# adc.net
KiCad netlist of a schematic drawn in Altium Designer
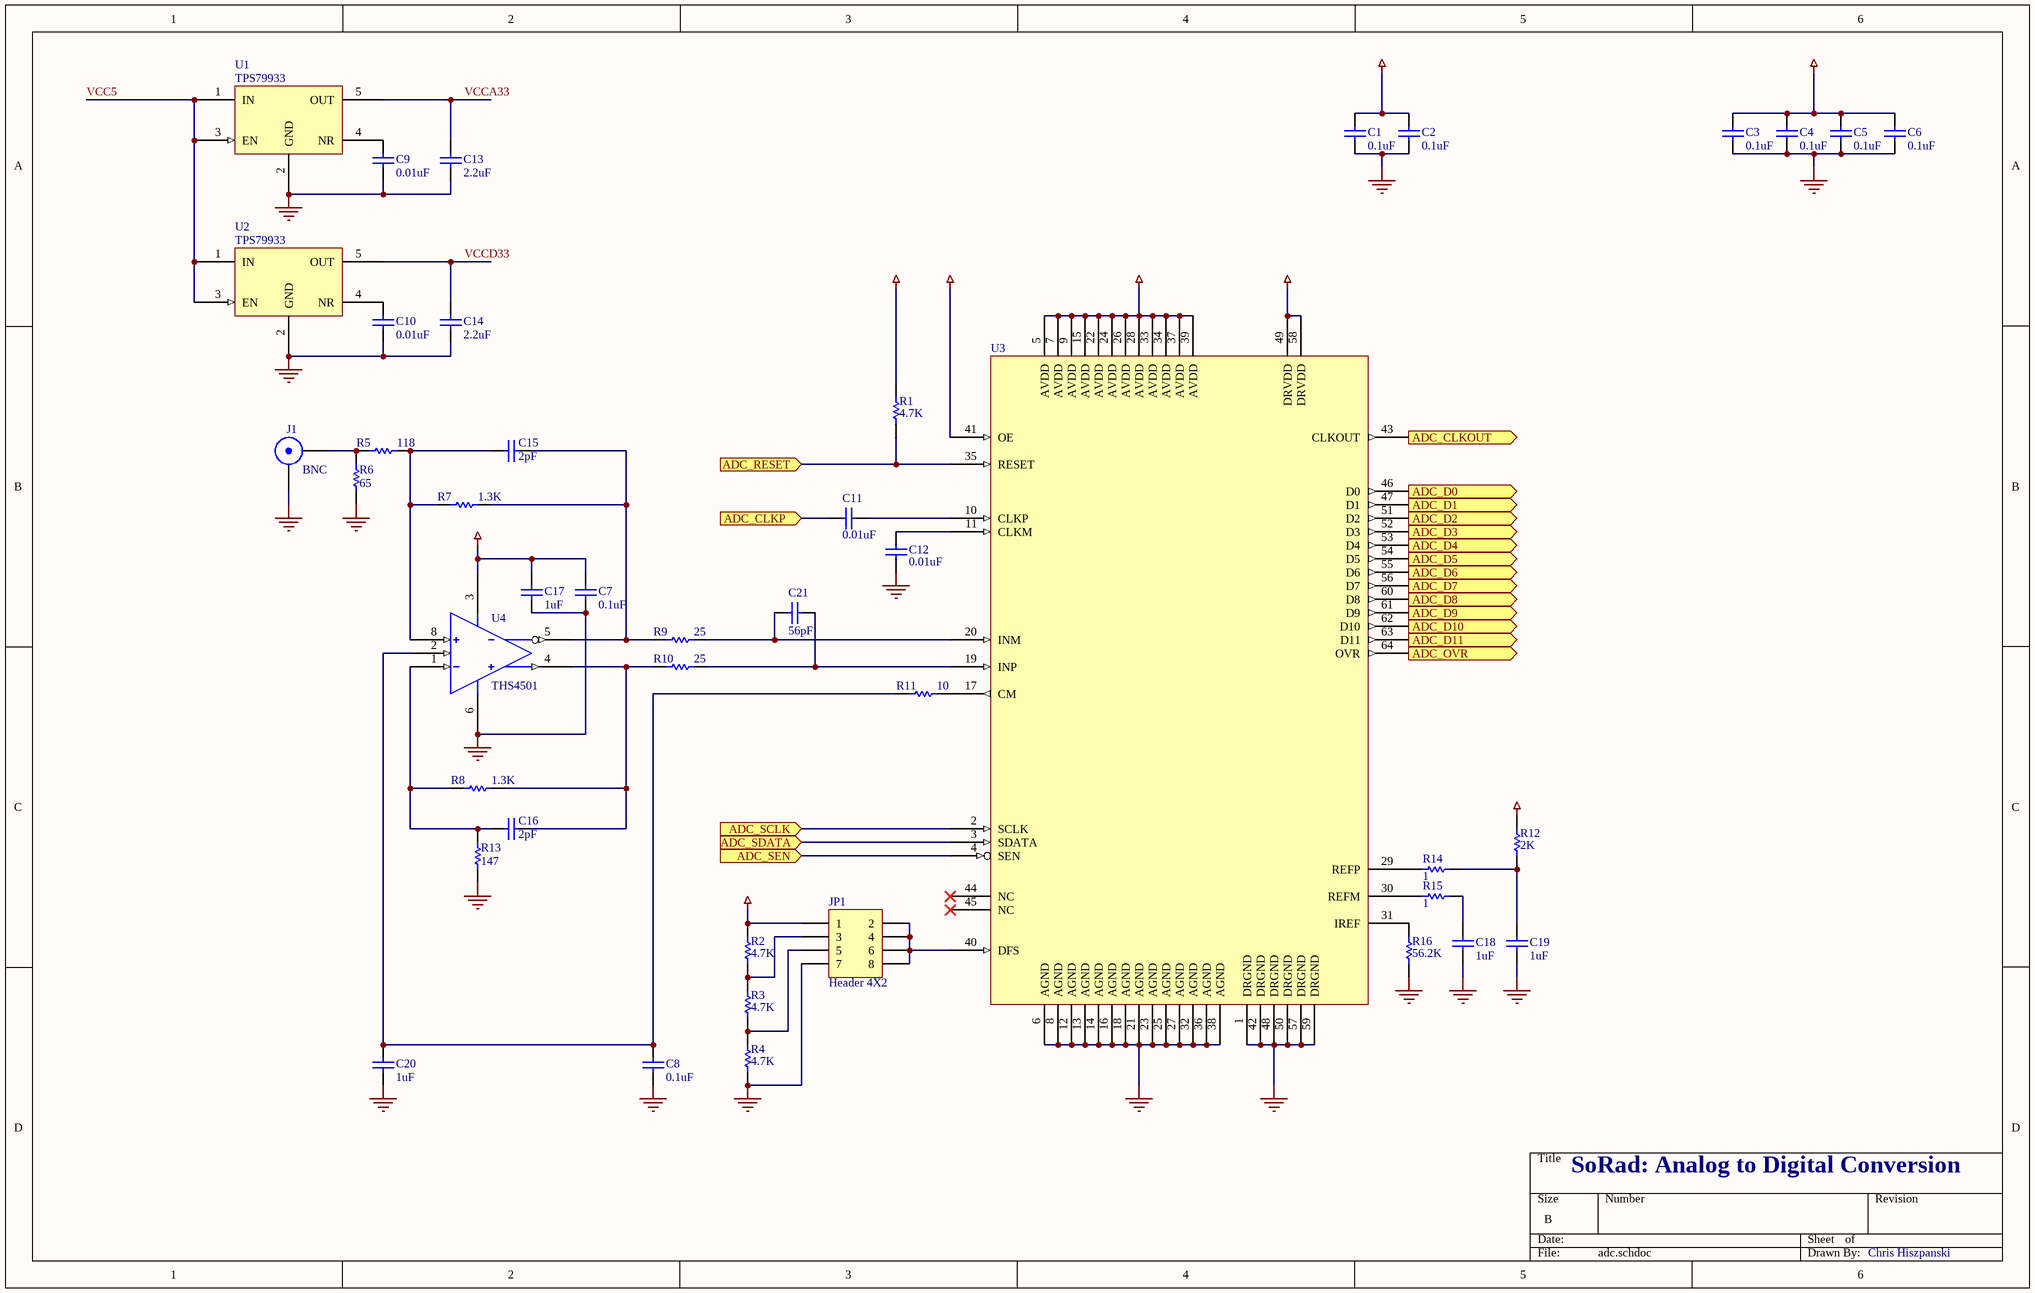
[diagram p0: adc.schdoc]

(export (version "E")
  (design (tool "Eeschema 10.0.6"))
  (components
    (comp (ref "C1")
      (value "0.1uF")
      (footprint "CC2012-0805")
      (description "Capacitor")
      (fields
        (field (name "DISTRIBUTOR PART NUMBER") "PCC1843CT-ND")
        (field (name "MANUFACTURER") "Panasonic")
        (field (name "PUBLISHER") "Altium Limited")
      )
      (libsource (lib "Miscellaneous Devices") (part "Cap"))
    )
    (comp (ref "C2")
      (value "0.1uF")
      (footprint "CC2012-0805")
      (description "Capacitor")
      (fields
        (field (name "DISTRIBUTOR PART NUMBER") "PCC1843CT-ND")
        (field (name "MANUFACTURER") "Panasonic")
        (field (name "PUBLISHER") "Altium Limited")
      )
      (libsource (lib "Miscellaneous Devices") (part "Cap"))
    )
    (comp (ref "C3")
      (value "0.1uF")
      (footprint "CC2012-0805")
      (description "Capacitor")
      (fields
        (field (name "DISTRIBUTOR PART NUMBER") "PCC1843CT-ND")
        (field (name "MANUFACTURER") "Panasonic")
        (field (name "PUBLISHER") "Altium Limited")
      )
      (libsource (lib "Miscellaneous Devices") (part "Cap"))
    )
    (comp (ref "C4")
      (value "0.1uF")
      (footprint "CC2012-0805")
      (description "Capacitor")
      (fields
        (field (name "DISTRIBUTOR PART NUMBER") "PCC1843CT-ND")
        (field (name "MANUFACTURER") "Panasonic")
        (field (name "PUBLISHER") "Altium Limited")
      )
      (libsource (lib "Miscellaneous Devices") (part "Cap"))
    )
    (comp (ref "C5")
      (value "0.1uF")
      (footprint "CC2012-0805")
      (description "Capacitor")
      (fields
        (field (name "DISTRIBUTOR PART NUMBER") "PCC1843CT-ND")
        (field (name "MANUFACTURER") "Panasonic")
        (field (name "PUBLISHER") "Altium Limited")
      )
      (libsource (lib "Miscellaneous Devices") (part "Cap"))
    )
    (comp (ref "C6")
      (value "0.1uF")
      (footprint "CC2012-0805")
      (description "Capacitor")
      (fields
        (field (name "DISTRIBUTOR PART NUMBER") "PCC1843CT-ND")
        (field (name "MANUFACTURER") "Panasonic")
        (field (name "PUBLISHER") "Altium Limited")
      )
      (libsource (lib "Miscellaneous Devices") (part "Cap"))
    )
    (comp (ref "C7")
      (value "0.1uF")
      (footprint "CC2012-0805")
      (description "Capacitor")
      (fields
        (field (name "DISTRIBUTOR PART NUMBER") "PCC1843CT-ND")
        (field (name "MANUFACTURER") "Panasonic")
        (field (name "PUBLISHER") "Altium Limited")
      )
      (libsource (lib "Miscellaneous Devices") (part "Cap"))
    )
    (comp (ref "C8")
      (value "0.1uF")
      (footprint "CC2012-0805")
      (description "Capacitor")
      (fields
        (field (name "DISTRIBUTOR PART NUMBER") "PCC1843CT-ND")
        (field (name "MANUFACTURER") "Panasonic")
        (field (name "PUBLISHER") "Altium Limited")
      )
      (libsource (lib "Miscellaneous Devices") (part "Cap"))
    )
    (comp (ref "C9")
      (value "0.01uF")
      (footprint "CC2012-0805")
      (description "Capacitor")
      (fields
        (field (name "DISTRIBUTOR PART NUMBER") "PCC1858CT-ND")
        (field (name "MANUFACTURER") "Panasonic")
        (field (name "PUBLISHER") "Altium Limited")
      )
      (libsource (lib "Miscellaneous Devices") (part "Cap"))
    )
    (comp (ref "C10")
      (value "0.01uF")
      (footprint "CC2012-0805")
      (description "Capacitor")
      (fields
        (field (name "DISTRIBUTOR PART NUMBER") "PCC1858CT-ND")
        (field (name "MANUFACTURER") "Panasonic")
        (field (name "PUBLISHER") "Altium Limited")
      )
      (libsource (lib "Miscellaneous Devices") (part "Cap"))
    )
    (comp (ref "C11")
      (value "0.01uF")
      (footprint "CC2012-0805")
      (description "Capacitor")
      (fields
        (field (name "DISTRIBUTOR PART NUMBER") "PCC1858CT-ND")
        (field (name "MANUFACTURER") "Panasonic")
        (field (name "PUBLISHER") "Altium Limited")
      )
      (libsource (lib "Miscellaneous Devices") (part "Cap"))
    )
    (comp (ref "C12")
      (value "0.01uF")
      (footprint "CC2012-0805")
      (description "Capacitor")
      (fields
        (field (name "DISTRIBUTOR PART NUMBER") "PCC1858CT-ND")
        (field (name "MANUFACTURER") "Panasonic")
        (field (name "PUBLISHER") "Altium Limited")
      )
      (libsource (lib "Miscellaneous Devices") (part "Cap"))
    )
    (comp (ref "C13")
      (value "2.2uF")
      (footprint "CC3216-1206")
      (description "Capacitor")
      (fields
        (field (name "DISTRIBUTOR PART NUMBER") "PCC1898CT-ND")
        (field (name "MANUFACTURER") "Panasonic")
        (field (name "PUBLISHER") "Altium Limited")
      )
      (libsource (lib "Miscellaneous Devices") (part "Cap"))
    )
    (comp (ref "C14")
      (value "2.2uF")
      (footprint "CC3216-1206")
      (description "Capacitor")
      (fields
        (field (name "DISTRIBUTOR PART NUMBER") "PCC1898CT-ND")
        (field (name "MANUFACTURER") "Panasonic")
        (field (name "PUBLISHER") "Altium Limited")
      )
      (libsource (lib "Miscellaneous Devices") (part "Cap"))
    )
    (comp (ref "C15")
      (value "2pF")
      (footprint "CC2012-0805")
      (description "Capacitor")
      (fields
        (field (name "DISTRIBUTOR PART NUMBER") "338-1096-ND")
        (field (name "MANUFACTURER") "Cornell Dubilier")
        (field (name "PUBLISHER") "Altium Limited")
      )
      (libsource (lib "Miscellaneous Devices") (part "Cap"))
    )
    (comp (ref "C16")
      (value "2pF")
      (footprint "CC2012-0805")
      (description "Capacitor")
      (fields
        (field (name "DISTRIBUTOR PART NUMBER") "338-1096-ND")
        (field (name "MANUFACTURER") "Cornell Dubilier")
        (field (name "PUBLISHER") "Altium Limited")
      )
      (libsource (lib "Miscellaneous Devices") (part "Cap"))
    )
    (comp (ref "C17")
      (value "1uF")
      (footprint "CC2012-0805")
      (description "Capacitor")
      (fields
        (field (name "MANUFACTURER") "Panasonic")
        (field (name "DISTRIBUTOR PART NUMBER") "PCC1849CT-ND")
        (field (name "PUBLISHER") "Altium Limited")
      )
      (libsource (lib "Miscellaneous Devices") (part "Cap"))
    )
    (comp (ref "C18")
      (value "1uF")
      (footprint "CC2012-0805")
      (description "Capacitor")
      (fields
        (field (name "MANUFACTURER") "Panasonic")
        (field (name "DISTRIBUTOR PART NUMBER") "PCC1849CT-ND")
        (field (name "PUBLISHER") "Altium Limited")
      )
      (libsource (lib "Miscellaneous Devices") (part "Cap"))
    )
    (comp (ref "C19")
      (value "1uF")
      (footprint "CC2012-0805")
      (description "Capacitor")
      (fields
        (field (name "MANUFACTURER") "Panasonic")
        (field (name "DISTRIBUTOR PART NUMBER") "PCC1849CT-ND")
        (field (name "PUBLISHER") "Altium Limited")
      )
      (libsource (lib "Miscellaneous Devices") (part "Cap"))
    )
    (comp (ref "C20")
      (value "1uF")
      (footprint "CC2012-0805")
      (description "Capacitor")
      (fields
        (field (name "MANUFACTURER") "Panasonic")
        (field (name "DISTRIBUTOR PART NUMBER") "PCC1849CT-ND")
        (field (name "PUBLISHER") "Altium Limited")
      )
      (libsource (lib "Miscellaneous Devices") (part "Cap"))
    )
    (comp (ref "C21")
      (value "56pF")
      (footprint "CC2012-0805")
      (description "Capacitor")
      (fields
        (field (name "DISTRIBUTOR PART NUMBER") "311-1108-1-ND")
        (field (name "MANUFACTURER") "Yageo")
        (field (name "PUBLISHER") "Altium Limited")
      )
      (libsource (lib "Miscellaneous Devices") (part "Cap"))
    )
    (comp (ref "J1")
      (value "BNC")
      (footprint "BNC_RA CON")
      (description "BNC Elbow Connector")
      (fields
        (field (name "DISTRIBUTOR PART NUMBER") "A24486-ND")
        (field (name "MANUFACTURER") "Amp")
        (field (name "PUBLISHER") "Altium Limited")
      )
      (libsource (lib "Miscellaneous Connectors") (part "BNC"))
    )
    (comp (ref "JP1")
      (value "Header 4X2")
      (footprint "HDR2X4")
      (description "Header, 4-Pin, Dual row")
      (fields (field (name "DISTRIBUTOR PART NUMBER") "NA") (field (name "PUBLISHER") "Altium Limited"))
      (libsource (lib "Miscellaneous Connectors") (part "Header 4X2"))
    )
    (comp (ref "R1")
      (value "4.7K")
      (footprint "CR2012-0805")
      (description "Resistor")
      (fields
        (field (name "MANUFACTURER") "Generic Components")
        (field (name "DISTRIBUTOR PART NUMBER") "541-4.7KACT-ND")
        (field (name "PUBLISHER") "Altium Limited")
      )
      (libsource (lib "") (part "Res1_1"))
    )
    (comp (ref "R2")
      (value "4.7K")
      (footprint "CR2012-0805")
      (description "Resistor")
      (fields
        (field (name "MANUFACTURER") "Generic Components")
        (field (name "DISTRIBUTOR PART NUMBER") "541-4.7KACT-ND")
        (field (name "PUBLISHER") "Altium Limited")
      )
      (libsource (lib "") (part "Res1_1"))
    )
    (comp (ref "R3")
      (value "4.7K")
      (footprint "CR2012-0805")
      (description "Resistor")
      (fields
        (field (name "MANUFACTURER") "Generic Components")
        (field (name "DISTRIBUTOR PART NUMBER") "541-4.7KACT-ND")
        (field (name "PUBLISHER") "Altium Limited")
      )
      (libsource (lib "") (part "Res1_1"))
    )
    (comp (ref "R4")
      (value "4.7K")
      (footprint "CR2012-0805")
      (description "Resistor")
      (fields
        (field (name "MANUFACTURER") "Generic Components")
        (field (name "DISTRIBUTOR PART NUMBER") "541-4.7KACT-ND")
        (field (name "PUBLISHER") "Altium Limited")
      )
      (libsource (lib "") (part "Res1_1"))
    )
    (comp (ref "R5")
      (value "118")
      (footprint "CC2012-0805")
      (description "Resistor")
      (fields
        (field (name "DISTRIBUTOR PART NUMBER") "311-118CCT-ND")
        (field (name "MANUFACTURER") "Yageo")
        (field (name "PUBLISHER") "Altium Limited")
      )
      (libsource (lib "Miscellaneous Devices") (part "Res1"))
    )
    (comp (ref "R6")
      (value "65")
      (footprint "CC2012-0805")
      (description "Resistor")
      (fields
        (field (name "DISTRIBUTOR PART NUMBER") "311-64.9CCT-ND")
        (field (name "MANUFACTURER") "Yageo")
        (field (name "PUBLISHER") "Altium Limited")
      )
      (libsource (lib "Miscellaneous Devices") (part "Res1"))
    )
    (comp (ref "R7")
      (value "1.3K")
      (footprint "CC2012-0805")
      (description "Resistor")
      (fields
        (field (name "DISTRIBUTOR PART NUMBER") "RHM1.30KCCT-ND")
        (field (name "MANUFACTURER") "Rohm")
        (field (name "PUBLISHER") "Altium Limited")
      )
      (libsource (lib "Miscellaneous Devices") (part "Res1"))
    )
    (comp (ref "R8")
      (value "1.3K")
      (footprint "CC2012-0805")
      (description "Resistor")
      (fields
        (field (name "DISTRIBUTOR PART NUMBER") "RHM1.30KCCT-ND")
        (field (name "MANUFACTURER") "Rohm")
        (field (name "PUBLISHER") "Altium Limited")
      )
      (libsource (lib "Miscellaneous Devices") (part "Res1"))
    )
    (comp (ref "R9")
      (value "25")
      (footprint "CC2012-0805")
      (description "Resistor")
      (fields
        (field (name "DISTRIBUTOR PART NUMBER") "541-24.9CCT-ND")
        (field (name "MANUFACTURER") "Vishay/Dale")
        (field (name "PUBLISHER") "Altium Limited")
      )
      (libsource (lib "Miscellaneous Devices") (part "Res1"))
    )
    (comp (ref "R10")
      (value "25")
      (footprint "CC2012-0805")
      (description "Resistor")
      (fields
        (field (name "DISTRIBUTOR PART NUMBER") "541-24.9CCT-ND")
        (field (name "MANUFACTURER") "Vishay/Dale")
        (field (name "PUBLISHER") "Altium Limited")
      )
      (libsource (lib "Miscellaneous Devices") (part "Res1"))
    )
    (comp (ref "R11")
      (value "10")
      (footprint "CC2012-0805")
      (description "Resistor")
      (fields
        (field (name "DISTRIBUTOR PART NUMBER") "311-10.0CRCT-ND")
        (field (name "MANUFACTURER") "Yageo")
        (field (name "PUBLISHER") "Altium Limited")
      )
      (libsource (lib "Miscellaneous Devices") (part "Res1"))
    )
    (comp (ref "R12")
      (value "2K")
      (footprint "CC2012-0805")
      (description "Resistor")
      (fields
        (field (name "DISTRIBUTOR PART NUMBER") "311-2.00KCRCT-ND")
        (field (name "MANUFACTURER") "Yageo")
        (field (name "PUBLISHER") "Altium Limited")
      )
      (libsource (lib "Miscellaneous Devices") (part "Res1"))
    )
    (comp (ref "R13")
      (value "147")
      (footprint "CC2012-0805")
      (description "Resistor")
      (fields
        (field (name "MANUFACTURER") "Yageo")
        (field (name "DISTRIBUTOR PART NUMBER") "311-147CRCT-ND")
        (field (name "PUBLISHER") "Altium Limited")
      )
      (libsource (lib "Miscellaneous Devices") (part "Res1"))
    )
    (comp (ref "R14")
      (value "1")
      (footprint "CC2012-0805")
      (description "Resistor")
      (fields
        (field (name "DISTRIBUTOR PART NUMBER") "311-1.00CRCT-ND")
        (field (name "MANUFACTURER") "Yageo")
        (field (name "PUBLISHER") "Altium Limited")
      )
      (libsource (lib "Miscellaneous Devices") (part "Res1"))
    )
    (comp (ref "R15")
      (value "1")
      (footprint "CC2012-0805")
      (description "Resistor")
      (fields
        (field (name "DISTRIBUTOR PART NUMBER") "311-1.00CRCT-ND")
        (field (name "MANUFACTURER") "Yageo")
        (field (name "PUBLISHER") "Altium Limited")
      )
      (libsource (lib "Miscellaneous Devices") (part "Res1"))
    )
    (comp (ref "R16")
      (value "56.2K")
      (footprint "CC2012-0805")
      (description "Resistor")
      (fields
        (field (name "DISTRIBUTOR PART NUMBER") "311-56.2KCRCT-ND")
        (field (name "MANUFACTURER") "Yageo")
        (field (name "PUBLISHER") "Altium Limited")
      )
      (libsource (lib "Miscellaneous Devices") (part "Res1"))
    )
    (comp (ref "U1")
      (value "TPS79933")
      (footprint "SO-G5/P.95")
      (description "LDO Voltage Regulator")
      (fields
        (field (name "DISTRIBUTOR PART NUMBER") "296-17783-1-ND")
        (field (name "MANUFACTURER") "Texas Instruments")
      )
      (libsource (lib "minisdr") (part "TPS799xx"))
    )
    (comp (ref "U2")
      (value "TPS79933")
      (footprint "SO-G5/P.95")
      (description "LDO Voltage Regulator")
      (fields
        (field (name "DISTRIBUTOR PART NUMBER") "296-17783-1-ND")
        (field (name "MANUFACTURER") "Texas Instruments")
      )
      (libsource (lib "minisdr") (part "TPS799xx"))
    )
    (comp (ref "U3")
      (value "~")
      (footprint "HQFP64")
      (description "ADC 12BIT 125MSPS")
      (fields
        (field (name "MANUFACTURER") "Texas Instruments")
        (field (name "MANUFACTURER PART NUMBER") "ADS5520IPAP")
      )
      (libsource (lib "minisdr") (part "ADS5520"))
    )
    (comp (ref "U4")
      (value "THS4501")
      (footprint "SOIC8")
      (description "Differential Amplifier")
      (fields
        (field (name "DISTRIBUTOR PART NUMBER") "296-12936-5-ND")
        (field (name "MANUFACTURER") "Texas Instruments")
      )
      (libsource (lib "minisdr") (part "THS4501"))
    )
  )
  (nets
    (net (code "1") (name "/ADC_CLKOUT") (class "Default")
      (node (ref "U3") (pin "43") (pinfunction "CLKOUT_43") (pintype "output"))
    )
    (net (code "2") (name "/ADC_CLKP") (class "Default")
      (node (ref "C11") (pin "2") (pinfunction "2_2") (pintype "passive"))
    )
    (net (code "3") (name "/ADC_D0") (class "Default")
      (node (ref "U3") (pin "46") (pinfunction "D0_46") (pintype "output"))
    )
    (net (code "4") (name "/ADC_D1") (class "Default")
      (node (ref "U3") (pin "47") (pinfunction "D1_47") (pintype "output"))
    )
    (net (code "5") (name "/ADC_D2") (class "Default")
      (node (ref "U3") (pin "51") (pinfunction "D2_51") (pintype "output"))
    )
    (net (code "6") (name "/ADC_D3") (class "Default")
      (node (ref "U3") (pin "52") (pinfunction "D3_52") (pintype "output"))
    )
    (net (code "7") (name "/ADC_D4") (class "Default")
      (node (ref "U3") (pin "53") (pinfunction "D4_53") (pintype "output"))
    )
    (net (code "8") (name "/ADC_D5") (class "Default")
      (node (ref "U3") (pin "54") (pinfunction "D5_54") (pintype "output"))
    )
    (net (code "9") (name "/ADC_D6") (class "Default")
      (node (ref "U3") (pin "55") (pinfunction "D6_55") (pintype "output"))
    )
    (net (code "10") (name "/ADC_D7") (class "Default")
      (node (ref "U3") (pin "56") (pinfunction "D7_56") (pintype "output"))
    )
    (net (code "11") (name "/ADC_D8") (class "Default")
      (node (ref "U3") (pin "60") (pinfunction "D8_60") (pintype "output"))
    )
    (net (code "12") (name "/ADC_D9") (class "Default")
      (node (ref "U3") (pin "61") (pinfunction "D9_61") (pintype "output"))
    )
    (net (code "13") (name "/ADC_D10") (class "Default")
      (node (ref "U3") (pin "62") (pinfunction "D10_62") (pintype "output"))
    )
    (net (code "14") (name "/ADC_D11") (class "Default")
      (node (ref "U3") (pin "63") (pinfunction "D11_63") (pintype "output"))
    )
    (net (code "15") (name "/ADC_OVR") (class "Default")
      (node (ref "U3") (pin "64") (pinfunction "OVR_64") (pintype "output"))
    )
    (net (code "16") (name "/ADC_RESET") (class "Default")
      (node (ref "R1") (pin "1") (pinfunction "1_1") (pintype "passive"))
      (node (ref "U3") (pin "35") (pinfunction "RESET_35") (pintype "input"))
    )
    (net (code "17") (name "/ADC_SCLK") (class "Default")
      (node (ref "U3") (pin "2") (pinfunction "SCLK_2") (pintype "input"))
    )
    (net (code "18") (name "/ADC_SDATA") (class "Default")
      (node (ref "U3") (pin "3") (pinfunction "SDATA_3") (pintype "input"))
    )
    (net (code "19") (name "/ADC_SEN") (class "Default")
      (node (ref "U3") (pin "4") (pinfunction "SEN_4") (pintype "input"))
    )
    (net (code "20") (name "GND") (class "Default")
      (node (ref "C1") (pin "1") (pinfunction "1_1") (pintype "passive"))
      (node (ref "C10") (pin "1") (pinfunction "1_1") (pintype "passive"))
      (node (ref "C12") (pin "2") (pinfunction "2_2") (pintype "passive"))
      (node (ref "C13") (pin "1") (pinfunction "1_1") (pintype "passive"))
      (node (ref "C14") (pin "1") (pinfunction "1_1") (pintype "passive"))
      (node (ref "C17") (pin "1") (pinfunction "1_1") (pintype "passive"))
      (node (ref "C18") (pin "1") (pinfunction "1_1") (pintype "passive"))
      (node (ref "C19") (pin "1") (pinfunction "1_1") (pintype "passive"))
      (node (ref "C2") (pin "1") (pinfunction "1_1") (pintype "passive"))
      (node (ref "C20") (pin "1") (pinfunction "1_1") (pintype "passive"))
      (node (ref "C3") (pin "1") (pinfunction "1_1") (pintype "passive"))
      (node (ref "C4") (pin "1") (pinfunction "1_1") (pintype "passive"))
      (node (ref "C5") (pin "1") (pinfunction "1_1") (pintype "passive"))
      (node (ref "C6") (pin "1") (pinfunction "1_1") (pintype "passive"))
      (node (ref "C7") (pin "1") (pinfunction "1_1") (pintype "passive"))
      (node (ref "C8") (pin "1") (pinfunction "1_1") (pintype "passive"))
      (node (ref "C9") (pin "1") (pinfunction "1_1") (pintype "passive"))
      (node (ref "J1") (pin "2") (pinfunction "Y_2") (pintype "passive"))
      (node (ref "JP1") (pin "7") (pinfunction "7_7") (pintype "passive"))
      (node (ref "R13") (pin "2") (pinfunction "2_2") (pintype "passive"))
      (node (ref "R16") (pin "2") (pinfunction "2_2") (pintype "passive"))
      (node (ref "R4") (pin "1") (pinfunction "1_1") (pintype "passive"))
      (node (ref "R6") (pin "2") (pinfunction "2_2") (pintype "passive"))
      (node (ref "U1") (pin "2") (pinfunction "GND_2") (pintype "power_in"))
      (node (ref "U2") (pin "2") (pinfunction "GND_2") (pintype "power_in"))
      (node (ref "U3") (pin "1") (pinfunction "DRGND_1") (pintype "power_in"))
      (node (ref "U3") (pin "12") (pinfunction "AGND_12") (pintype "power_in"))
      (node (ref "U3") (pin "13") (pinfunction "AGND_13") (pintype "power_in"))
      (node (ref "U3") (pin "14") (pinfunction "AGND_14") (pintype "power_in"))
      (node (ref "U3") (pin "16") (pinfunction "AGND_16") (pintype "power_in"))
      (node (ref "U3") (pin "18") (pinfunction "AGND_18") (pintype "power_in"))
      (node (ref "U3") (pin "21") (pinfunction "AGND_21") (pintype "power_in"))
      (node (ref "U3") (pin "23") (pinfunction "AGND_23") (pintype "power_in"))
      (node (ref "U3") (pin "25") (pinfunction "AGND_25") (pintype "power_in"))
      (node (ref "U3") (pin "27") (pinfunction "AGND_27") (pintype "power_in"))
      (node (ref "U3") (pin "32") (pinfunction "AGND_32") (pintype "power_in"))
      (node (ref "U3") (pin "36") (pinfunction "AGND_36") (pintype "power_in"))
      (node (ref "U3") (pin "38") (pinfunction "AGND_38") (pintype "power_in"))
      (node (ref "U3") (pin "42") (pinfunction "DRGND_42") (pintype "power_in"))
      (node (ref "U3") (pin "48") (pinfunction "DRGND_48") (pintype "power_in"))
      (node (ref "U3") (pin "50") (pinfunction "DRGND_50") (pintype "power_in"))
      (node (ref "U3") (pin "57") (pinfunction "DRGND_57") (pintype "power_in"))
      (node (ref "U3") (pin "59") (pinfunction "DRGND_59") (pintype "power_in"))
      (node (ref "U3") (pin "6") (pinfunction "AGND_6") (pintype "power_in"))
      (node (ref "U3") (pin "8") (pinfunction "AGND_8") (pintype "power_in"))
      (node (ref "U4") (pin "6") (pinfunction "Vs-_6") (pintype "power_in"))
    )
    (net (code "21") (name "Net-(C18-Pad2)") (class "Default")
      (node (ref "C18") (pin "2") (pinfunction "2_2") (pintype "passive"))
      (node (ref "R15") (pin "2") (pinfunction "2_2") (pintype "passive"))
    )
    (net (code "22") (name "Net-(C19-Pad2)") (class "Default")
      (node (ref "C19") (pin "2") (pinfunction "2_2") (pintype "passive"))
      (node (ref "R12") (pin "2") (pinfunction "2_2") (pintype "passive"))
      (node (ref "R14") (pin "2") (pinfunction "2_2") (pintype "passive"))
    )
    (net (code "23") (name "Net-(J1-X)") (class "Default")
      (node (ref "J1") (pin "1") (pinfunction "X_1") (pintype "passive"))
      (node (ref "R5") (pin "2") (pinfunction "2_2") (pintype "passive"))
      (node (ref "R6") (pin "1") (pinfunction "1_1") (pintype "passive"))
    )
    (net (code "24") (name "Net-(JP1-Pad3)") (class "Default")
      (node (ref "JP1") (pin "3") (pinfunction "3_3") (pintype "passive"))
      (node (ref "R2") (pin "1") (pinfunction "1_1") (pintype "passive"))
      (node (ref "R3") (pin "2") (pinfunction "2_2") (pintype "passive"))
    )
    (net (code "25") (name "Net-(JP1-Pad5)") (class "Default")
      (node (ref "JP1") (pin "5") (pinfunction "5_5") (pintype "passive"))
      (node (ref "R3") (pin "1") (pinfunction "1_1") (pintype "passive"))
      (node (ref "R4") (pin "2") (pinfunction "2_2") (pintype "passive"))
    )
    (net (code "26") (name "Net-(U1-NR)") (class "Default")
      (node (ref "C9") (pin "2") (pinfunction "2_2") (pintype "passive"))
      (node (ref "U1") (pin "4") (pinfunction "NR_4") (pintype "passive"))
    )
    (net (code "27") (name "Net-(U2-NR)") (class "Default")
      (node (ref "C10") (pin "2") (pinfunction "2_2") (pintype "passive"))
      (node (ref "U2") (pin "4") (pinfunction "NR_4") (pintype "passive"))
    )
    (net (code "28") (name "Net-(U3-CLKM)") (class "Default")
      (node (ref "C12") (pin "1") (pinfunction "1_1") (pintype "passive"))
      (node (ref "U3") (pin "11") (pinfunction "CLKM_11") (pintype "input"))
    )
    (net (code "29") (name "Net-(U3-CLKP)") (class "Default")
      (node (ref "C11") (pin "1") (pinfunction "1_1") (pintype "passive"))
      (node (ref "U3") (pin "10") (pinfunction "CLKP_10") (pintype "input"))
    )
    (net (code "30") (name "Net-(U3-CM)") (class "Default")
      (node (ref "R11") (pin "1") (pinfunction "1_1") (pintype "passive"))
      (node (ref "U3") (pin "17") (pinfunction "CM_17") (pintype "output"))
    )
    (net (code "31") (name "Net-(U3-DFS)") (class "Default")
      (node (ref "JP1") (pin "2") (pinfunction "2_2") (pintype "passive"))
      (node (ref "JP1") (pin "4") (pinfunction "4_4") (pintype "passive"))
      (node (ref "JP1") (pin "6") (pinfunction "6_6") (pintype "passive"))
      (node (ref "JP1") (pin "8") (pinfunction "8_8") (pintype "passive"))
      (node (ref "U3") (pin "40") (pinfunction "DFS_40") (pintype "input"))
    )
    (net (code "32") (name "Net-(U3-INM)") (class "Default")
      (node (ref "C21") (pin "1") (pinfunction "1_1") (pintype "passive"))
      (node (ref "R9") (pin "1") (pinfunction "1_1") (pintype "passive"))
      (node (ref "U3") (pin "20") (pinfunction "INM_20") (pintype "input"))
    )
    (net (code "33") (name "Net-(U3-INP)") (class "Default")
      (node (ref "C21") (pin "2") (pinfunction "2_2") (pintype "passive"))
      (node (ref "R10") (pin "1") (pinfunction "1_1") (pintype "passive"))
      (node (ref "U3") (pin "19") (pinfunction "INP_19") (pintype "input"))
    )
    (net (code "34") (name "Net-(U3-IREF)") (class "Default")
      (node (ref "R16") (pin "1") (pinfunction "1_1") (pintype "passive"))
      (node (ref "U3") (pin "31") (pinfunction "IREF_31") (pintype "passive"))
    )
    (net (code "35") (name "Net-(U3-REFM)") (class "Default")
      (node (ref "R15") (pin "1") (pinfunction "1_1") (pintype "passive"))
      (node (ref "U3") (pin "30") (pinfunction "REFM_30") (pintype "passive"))
    )
    (net (code "36") (name "Net-(U3-REFP)") (class "Default")
      (node (ref "R14") (pin "1") (pinfunction "1_1") (pintype "passive"))
      (node (ref "U3") (pin "29") (pinfunction "REFP_29") (pintype "passive"))
    )
    (net (code "37") (name "Net-(U4-Vin+)") (class "Default")
      (node (ref "C15") (pin "2") (pinfunction "2_2") (pintype "passive"))
      (node (ref "R5") (pin "1") (pinfunction "1_1") (pintype "passive"))
      (node (ref "R7") (pin "2") (pinfunction "2_2") (pintype "passive"))
      (node (ref "U4") (pin "8") (pinfunction "Vin+_8") (pintype "input"))
    )
    (net (code "38") (name "Net-(U4-Vin-)") (class "Default")
      (node (ref "C16") (pin "2") (pinfunction "2_2") (pintype "passive"))
      (node (ref "R13") (pin "1") (pinfunction "1_1") (pintype "passive"))
      (node (ref "R8") (pin "2") (pinfunction "2_2") (pintype "passive"))
      (node (ref "U4") (pin "1") (pinfunction "Vin-_1") (pintype "input"))
    )
    (net (code "39") (name "Net-(U4-Vocm)") (class "Default")
      (node (ref "C20") (pin "2") (pinfunction "2_2") (pintype "passive"))
      (node (ref "C8") (pin "2") (pinfunction "2_2") (pintype "passive"))
      (node (ref "R11") (pin "2") (pinfunction "2_2") (pintype "passive"))
      (node (ref "U4") (pin "2") (pinfunction "Vocm_2") (pintype "input"))
    )
    (net (code "40") (name "Net-(U4-Vout+)") (class "Default")
      (node (ref "C16") (pin "1") (pinfunction "1_1") (pintype "passive"))
      (node (ref "R10") (pin "2") (pinfunction "2_2") (pintype "passive"))
      (node (ref "R8") (pin "1") (pinfunction "1_1") (pintype "passive"))
      (node (ref "U4") (pin "4") (pinfunction "Vout+_4") (pintype "output"))
    )
    (net (code "41") (name "Net-(U4-Vout-)") (class "Default")
      (node (ref "C15") (pin "1") (pinfunction "1_1") (pintype "passive"))
      (node (ref "R7") (pin "1") (pinfunction "1_1") (pintype "passive"))
      (node (ref "R9") (pin "2") (pinfunction "2_2") (pintype "passive"))
      (node (ref "U4") (pin "5") (pinfunction "Vout-_5") (pintype "output"))
    )
    (net (code "42") (name "VCC5") (class "Default")
      (node (ref "C17") (pin "2") (pinfunction "2_2") (pintype "passive"))
      (node (ref "C7") (pin "2") (pinfunction "2_2") (pintype "passive"))
      (node (ref "U1") (pin "1") (pinfunction "IN_1") (pintype "power_in"))
      (node (ref "U1") (pin "3") (pinfunction "EN_3") (pintype "input"))
      (node (ref "U2") (pin "1") (pinfunction "IN_1") (pintype "power_in"))
      (node (ref "U2") (pin "3") (pinfunction "EN_3") (pintype "input"))
      (node (ref "U4") (pin "3") (pinfunction "Vs+_3") (pintype "power_in"))
    )
    (net (code "43") (name "VCCA33") (class "Default")
      (node (ref "C13") (pin "2") (pinfunction "2_2") (pintype "passive"))
      (node (ref "C3") (pin "2") (pinfunction "2_2") (pintype "passive"))
      (node (ref "C4") (pin "2") (pinfunction "2_2") (pintype "passive"))
      (node (ref "C5") (pin "2") (pinfunction "2_2") (pintype "passive"))
      (node (ref "C6") (pin "2") (pinfunction "2_2") (pintype "passive"))
      (node (ref "R12") (pin "1") (pinfunction "1_1") (pintype "passive"))
      (node (ref "U1") (pin "5") (pinfunction "OUT_5") (pintype "power_in"))
      (node (ref "U3") (pin "15") (pinfunction "AVDD_15") (pintype "power_in"))
      (node (ref "U3") (pin "22") (pinfunction "AVDD_22") (pintype "power_in"))
      (node (ref "U3") (pin "24") (pinfunction "AVDD_24") (pintype "power_in"))
      (node (ref "U3") (pin "26") (pinfunction "AVDD_26") (pintype "power_in"))
      (node (ref "U3") (pin "28") (pinfunction "AVDD_28") (pintype "power_in"))
      (node (ref "U3") (pin "33") (pinfunction "AVDD_33") (pintype "power_in"))
      (node (ref "U3") (pin "34") (pinfunction "AVDD_34") (pintype "power_in"))
      (node (ref "U3") (pin "37") (pinfunction "AVDD_37") (pintype "power_in"))
      (node (ref "U3") (pin "39") (pinfunction "AVDD_39") (pintype "power_in"))
      (node (ref "U3") (pin "5") (pinfunction "AVDD_5") (pintype "power_in"))
      (node (ref "U3") (pin "7") (pinfunction "AVDD_7") (pintype "power_in"))
      (node (ref "U3") (pin "9") (pinfunction "AVDD_9") (pintype "power_in"))
    )
    (net (code "44") (name "VCCD33") (class "Default")
      (node (ref "C1") (pin "2") (pinfunction "2_2") (pintype "passive"))
      (node (ref "C14") (pin "2") (pinfunction "2_2") (pintype "passive"))
      (node (ref "C2") (pin "2") (pinfunction "2_2") (pintype "passive"))
      (node (ref "JP1") (pin "1") (pinfunction "1_1") (pintype "passive"))
      (node (ref "R1") (pin "2") (pinfunction "2_2") (pintype "passive"))
      (node (ref "R2") (pin "2") (pinfunction "2_2") (pintype "passive"))
      (node (ref "U2") (pin "5") (pinfunction "OUT_5") (pintype "power_in"))
      (node (ref "U3") (pin "41") (pinfunction "OE_41") (pintype "input"))
      (node (ref "U3") (pin "49") (pinfunction "DRVDD_49") (pintype "power_in"))
      (node (ref "U3") (pin "58") (pinfunction "DRVDD_58") (pintype "power_in"))
    )
    (net (code "45") (name "unconnected-(U3-NC-Pad44)") (class "Default")
      (node (ref "U3") (pin "44") (pinfunction "NC_44") (pintype "passive+no_connect"))
    )
    (net (code "46") (name "unconnected-(U3-NC-Pad45)") (class "Default")
      (node (ref "U3") (pin "45") (pinfunction "NC_45") (pintype "passive+no_connect"))
    )
  )
)
